# 3w-rgb-led-connector-mk-7_0.net
KiCad netlist of a schematic drawn in EAGLE
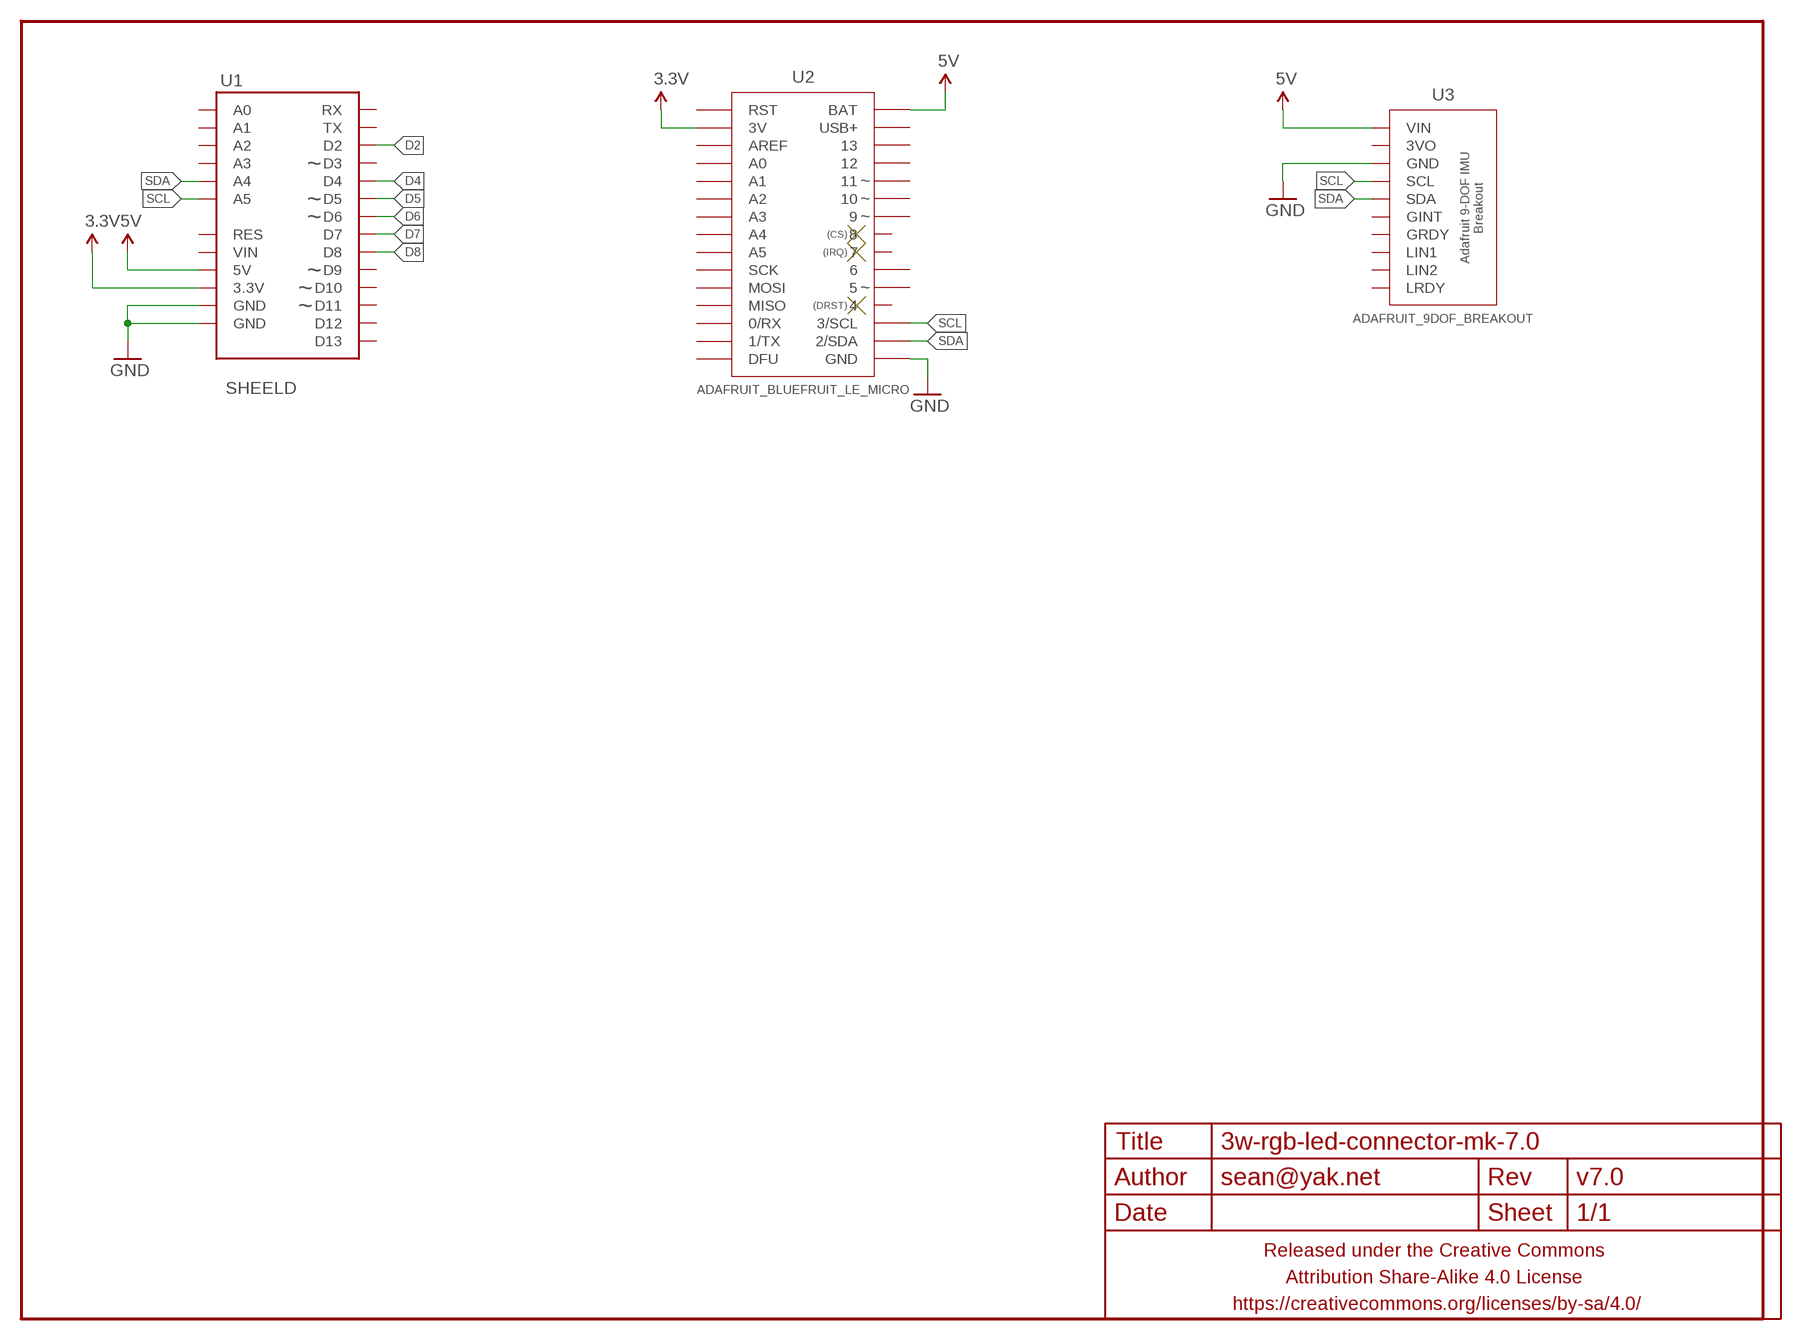
[diagram p0: schematic, sheet 1]

(export (version "E")
  (design (tool "Eeschema 10.0.6"))
  (components
    (comp (ref "FRAME1")
      (value "FRAME-LETTERNO_PACKAGE")
      (footprint "eagle-import:DUMMY")
      (fields (field (name "DESIGNER") "sean@yak.net") (field (name "VERSION") "v7.0"))
      (libsource (lib "eagle-import") (part "FRAME-LETTERNO_PACKAGE"))
    )
    (comp (ref "U1")
      (value "SHEELD")
      (footprint "eagle-import:ARDUINO_SHIELD_NOOUTLINE_INSIDE_SMALLER")
      (libsource (lib "eagle-import") (part "ARDUINO_SHIELD_SMALLER"))
    )
    (comp (ref "U2")
      (value "ADAFRUIT_BLUEFRUIT_LE_MICRO")
      (footprint "eagle-import:ADAFRUIT_BLUEFRUIT_LE_MICRO")
      (libsource (lib "eagle-import") (part "ADAFRUIT_BLUEFRUIT_LE_MICRO"))
    )
    (comp (ref "U3")
      (value "ADAFRUIT_9DOF_BREAKOUT")
      (footprint "eagle-import:ADAFRUIT_9DOF_BREAKOUT")
      (libsource (lib "eagle-import") (part "ADAFRUIT_9DOF_BREAKOUT"))
    )
  )
  (nets
    (net (code "1") (name "3.3V") (class "Default")
      (node (ref "U1") (pin "3.3V") (pinfunction "3.3V_3.3V") (pintype "bidirectional"))
      (node (ref "U2") (pin "3V3") (pinfunction "3V_3V3") (pintype "bidirectional"))
    )
    (net (code "2") (name "5V") (class "Default")
      (node (ref "U1") (pin "5V") (pinfunction "5V_5V") (pintype "bidirectional"))
      (node (ref "U2") (pin "BAT") (pinfunction "BAT_BAT") (pintype "bidirectional"))
      (node (ref "U3") (pin "VIN") (pinfunction "VIN_VIN") (pintype "bidirectional"))
    )
    (net (code "3") (name "D2") (class "Default")
      (node (ref "U1") (pin "D2") (pinfunction "D2_D2") (pintype "bidirectional"))
    )
    (net (code "4") (name "D4") (class "Default")
      (node (ref "U1") (pin "D4") (pinfunction "D4_D4") (pintype "bidirectional"))
    )
    (net (code "5") (name "D5") (class "Default")
      (node (ref "U1") (pin "D5") (pinfunction "D5_D5") (pintype "bidirectional"))
    )
    (net (code "6") (name "D6") (class "Default")
      (node (ref "U1") (pin "D6") (pinfunction "D6_D6") (pintype "bidirectional"))
    )
    (net (code "7") (name "D7") (class "Default")
      (node (ref "U1") (pin "D7") (pinfunction "D7_D7") (pintype "bidirectional"))
    )
    (net (code "8") (name "D8") (class "Default")
      (node (ref "U1") (pin "D8") (pinfunction "D8_D8") (pintype "bidirectional"))
    )
    (net (code "9") (name "GND") (class "Default")
      (node (ref "U1") (pin "GND@0") (pinfunction "GND_GND@0") (pintype "bidirectional"))
      (node (ref "U1") (pin "GND@1") (pinfunction "GND_GND@1") (pintype "bidirectional"))
      (node (ref "U2") (pin "GND@1") (pinfunction "GND_GND@1") (pintype "bidirectional"))
      (node (ref "U2") (pin "GND@2") (pinfunction "GND_GND@2") (pintype "bidirectional"))
      (node (ref "U2") (pin "GND@3") (pinfunction "GND_GND@3") (pintype "bidirectional"))
      (node (ref "U3") (pin "GND") (pinfunction "GND_GND") (pintype "bidirectional"))
    )
    (net (code "10") (name "SCL") (class "Default")
      (node (ref "U1") (pin "A5") (pinfunction "A5_A5") (pintype "bidirectional"))
      (node (ref "U2") (pin "3/SCL") (pinfunction "3/SCL_3/SCL") (pintype "bidirectional"))
      (node (ref "U3") (pin "SCL") (pinfunction "SCL_SCL") (pintype "bidirectional"))
    )
    (net (code "11") (name "SDA") (class "Default")
      (node (ref "U1") (pin "A4") (pinfunction "A4_A4") (pintype "bidirectional"))
      (node (ref "U2") (pin "2/SDA") (pinfunction "2/SDA_2/SDA") (pintype "bidirectional"))
      (node (ref "U3") (pin "SDA") (pinfunction "SDA_SDA") (pintype "bidirectional"))
    )
    (net (code "12") (name "unconnected-(U1-PadA0)") (class "Default")
      (node (ref "U1") (pin "A0") (pinfunction "A0_A0") (pintype "bidirectional"))
    )
    (net (code "13") (name "unconnected-(U1-PadA1)") (class "Default")
      (node (ref "U1") (pin "A1") (pinfunction "A1_A1") (pintype "bidirectional"))
    )
    (net (code "14") (name "unconnected-(U1-PadA2)") (class "Default")
      (node (ref "U1") (pin "A2") (pinfunction "A2_A2") (pintype "bidirectional"))
    )
    (net (code "15") (name "unconnected-(U1-PadA3)") (class "Default")
      (node (ref "U1") (pin "A3") (pinfunction "A3_A3") (pintype "bidirectional"))
    )
    (net (code "16") (name "unconnected-(U1-PadD3)") (class "Default")
      (node (ref "U1") (pin "D3") (pinfunction "D3_D3") (pintype "bidirectional"))
    )
    (net (code "17") (name "unconnected-(U1-PadD9)") (class "Default")
      (node (ref "U1") (pin "D9") (pinfunction "D9_D9") (pintype "bidirectional"))
    )
    (net (code "18") (name "unconnected-(U1-PadD10)") (class "Default")
      (node (ref "U1") (pin "D10") (pinfunction "D10_D10") (pintype "bidirectional"))
    )
    (net (code "19") (name "unconnected-(U1-PadD11)") (class "Default")
      (node (ref "U1") (pin "D11") (pinfunction "D11_D11") (pintype "bidirectional"))
    )
    (net (code "20") (name "unconnected-(U1-PadD12)") (class "Default")
      (node (ref "U1") (pin "D12") (pinfunction "D12_D12") (pintype "bidirectional"))
    )
    (net (code "21") (name "unconnected-(U1-PadD13)") (class "Default")
      (node (ref "U1") (pin "D13") (pinfunction "D13_D13") (pintype "bidirectional"))
    )
    (net (code "22") (name "unconnected-(U1-PadRES)") (class "Default")
      (node (ref "U1") (pin "RES") (pinfunction "RES_RES") (pintype "bidirectional"))
    )
    (net (code "23") (name "unconnected-(U1-PadRX)") (class "Default")
      (node (ref "U1") (pin "RX") (pinfunction "RX_RX") (pintype "bidirectional"))
    )
    (net (code "24") (name "unconnected-(U1-PadTX)") (class "Default")
      (node (ref "U1") (pin "TX") (pinfunction "TX_TX") (pintype "bidirectional"))
    )
    (net (code "25") (name "unconnected-(U1-PadVIN)") (class "Default")
      (node (ref "U1") (pin "VIN") (pinfunction "VIN_VIN") (pintype "bidirectional"))
    )
    (net (code "26") (name "unconnected-(U2-Pad0{slash}RX)") (class "Default")
      (node (ref "U2") (pin "0/RX") (pinfunction "0/RX_0/RX") (pintype "bidirectional"))
    )
    (net (code "27") (name "unconnected-(U2-Pad1{slash}TX)") (class "Default")
      (node (ref "U2") (pin "1/TX") (pinfunction "1/TX_1/TX") (pintype "bidirectional"))
    )
    (net (code "28") (name "unconnected-(U2-Pad4)") (class "Default")
      (node (ref "U2") (pin "4") (pinfunction "4_4") (pintype "bidirectional"))
    )
    (net (code "29") (name "unconnected-(U2-Pad5)") (class "Default")
      (node (ref "U2") (pin "5") (pinfunction "5_5") (pintype "bidirectional"))
    )
    (net (code "30") (name "unconnected-(U2-Pad6)") (class "Default")
      (node (ref "U2") (pin "6") (pinfunction "6_6") (pintype "bidirectional"))
    )
    (net (code "31") (name "unconnected-(U2-Pad7)") (class "Default")
      (node (ref "U2") (pin "7") (pinfunction "7_7") (pintype "bidirectional"))
    )
    (net (code "32") (name "unconnected-(U2-Pad8)") (class "Default")
      (node (ref "U2") (pin "8") (pinfunction "8_8") (pintype "bidirectional"))
    )
    (net (code "33") (name "unconnected-(U2-Pad9)") (class "Default")
      (node (ref "U2") (pin "9") (pinfunction "9_9") (pintype "bidirectional"))
    )
    (net (code "34") (name "unconnected-(U2-Pad10)") (class "Default")
      (node (ref "U2") (pin "10") (pinfunction "10_10") (pintype "bidirectional"))
    )
    (net (code "35") (name "unconnected-(U2-Pad11)") (class "Default")
      (node (ref "U2") (pin "11") (pinfunction "11_11") (pintype "bidirectional"))
    )
    (net (code "36") (name "unconnected-(U2-Pad12)") (class "Default")
      (node (ref "U2") (pin "12") (pinfunction "12_12") (pintype "bidirectional"))
    )
    (net (code "37") (name "unconnected-(U2-Pad13)") (class "Default")
      (node (ref "U2") (pin "13") (pinfunction "13_13") (pintype "bidirectional"))
    )
    (net (code "38") (name "unconnected-(U2-PadA0)") (class "Default")
      (node (ref "U2") (pin "A0") (pinfunction "A0_A0") (pintype "bidirectional"))
    )
    (net (code "39") (name "unconnected-(U2-PadA1)") (class "Default")
      (node (ref "U2") (pin "A1") (pinfunction "A1_A1") (pintype "bidirectional"))
    )
    (net (code "40") (name "unconnected-(U2-PadA2)") (class "Default")
      (node (ref "U2") (pin "A2") (pinfunction "A2_A2") (pintype "bidirectional"))
    )
    (net (code "41") (name "unconnected-(U2-PadA3)") (class "Default")
      (node (ref "U2") (pin "A3") (pinfunction "A3_A3") (pintype "bidirectional"))
    )
    (net (code "42") (name "unconnected-(U2-PadA4)") (class "Default")
      (node (ref "U2") (pin "A4") (pinfunction "A4_A4") (pintype "bidirectional"))
    )
    (net (code "43") (name "unconnected-(U2-PadA5)") (class "Default")
      (node (ref "U2") (pin "A5") (pinfunction "A5_A5") (pintype "bidirectional"))
    )
    (net (code "44") (name "unconnected-(U2-PadAREF)") (class "Default")
      (node (ref "U2") (pin "AREF") (pinfunction "AREF_AREF") (pintype "bidirectional"))
    )
    (net (code "45") (name "unconnected-(U2-PadDFU)") (class "Default")
      (node (ref "U2") (pin "DFU") (pinfunction "DFU_DFU") (pintype "bidirectional"))
    )
    (net (code "46") (name "unconnected-(U2-PadMISO)") (class "Default")
      (node (ref "U2") (pin "MISO") (pinfunction "MISO_MISO") (pintype "bidirectional"))
    )
    (net (code "47") (name "unconnected-(U2-PadMOSI)") (class "Default")
      (node (ref "U2") (pin "MOSI") (pinfunction "MOSI_MOSI") (pintype "bidirectional"))
    )
    (net (code "48") (name "unconnected-(U2-PadRST)") (class "Default")
      (node (ref "U2") (pin "RST") (pinfunction "RST_RST") (pintype "bidirectional"))
    )
    (net (code "49") (name "unconnected-(U2-PadSCK)") (class "Default")
      (node (ref "U2") (pin "SCK") (pinfunction "SCK_SCK") (pintype "bidirectional"))
    )
    (net (code "50") (name "unconnected-(U2-USB+-PadUSB)") (class "Default")
      (node (ref "U2") (pin "USB") (pinfunction "USB+_USB") (pintype "bidirectional"))
    )
    (net (code "51") (name "unconnected-(U3-Pad3VO)") (class "Default")
      (node (ref "U3") (pin "3VO") (pinfunction "3VO_3VO") (pintype "bidirectional"))
    )
    (net (code "52") (name "unconnected-(U3-PadGINT)") (class "Default")
      (node (ref "U3") (pin "GINT") (pinfunction "GINT_GINT") (pintype "bidirectional"))
    )
    (net (code "53") (name "unconnected-(U3-PadGRDY)") (class "Default")
      (node (ref "U3") (pin "GRDY") (pinfunction "GRDY_GRDY") (pintype "bidirectional"))
    )
    (net (code "54") (name "unconnected-(U3-PadLIN1)") (class "Default")
      (node (ref "U3") (pin "LIN1") (pinfunction "LIN1_LIN1") (pintype "bidirectional"))
    )
    (net (code "55") (name "unconnected-(U3-PadLIN2)") (class "Default")
      (node (ref "U3") (pin "LIN2") (pinfunction "LIN2_LIN2") (pintype "bidirectional"))
    )
    (net (code "56") (name "unconnected-(U3-PadLRDY)") (class "Default")
      (node (ref "U3") (pin "LRDY") (pinfunction "LRDY_LRDY") (pintype "bidirectional"))
    )
  )
)
